# pcb.net
KiCad netlist of a schematic drawn in EasyEDA
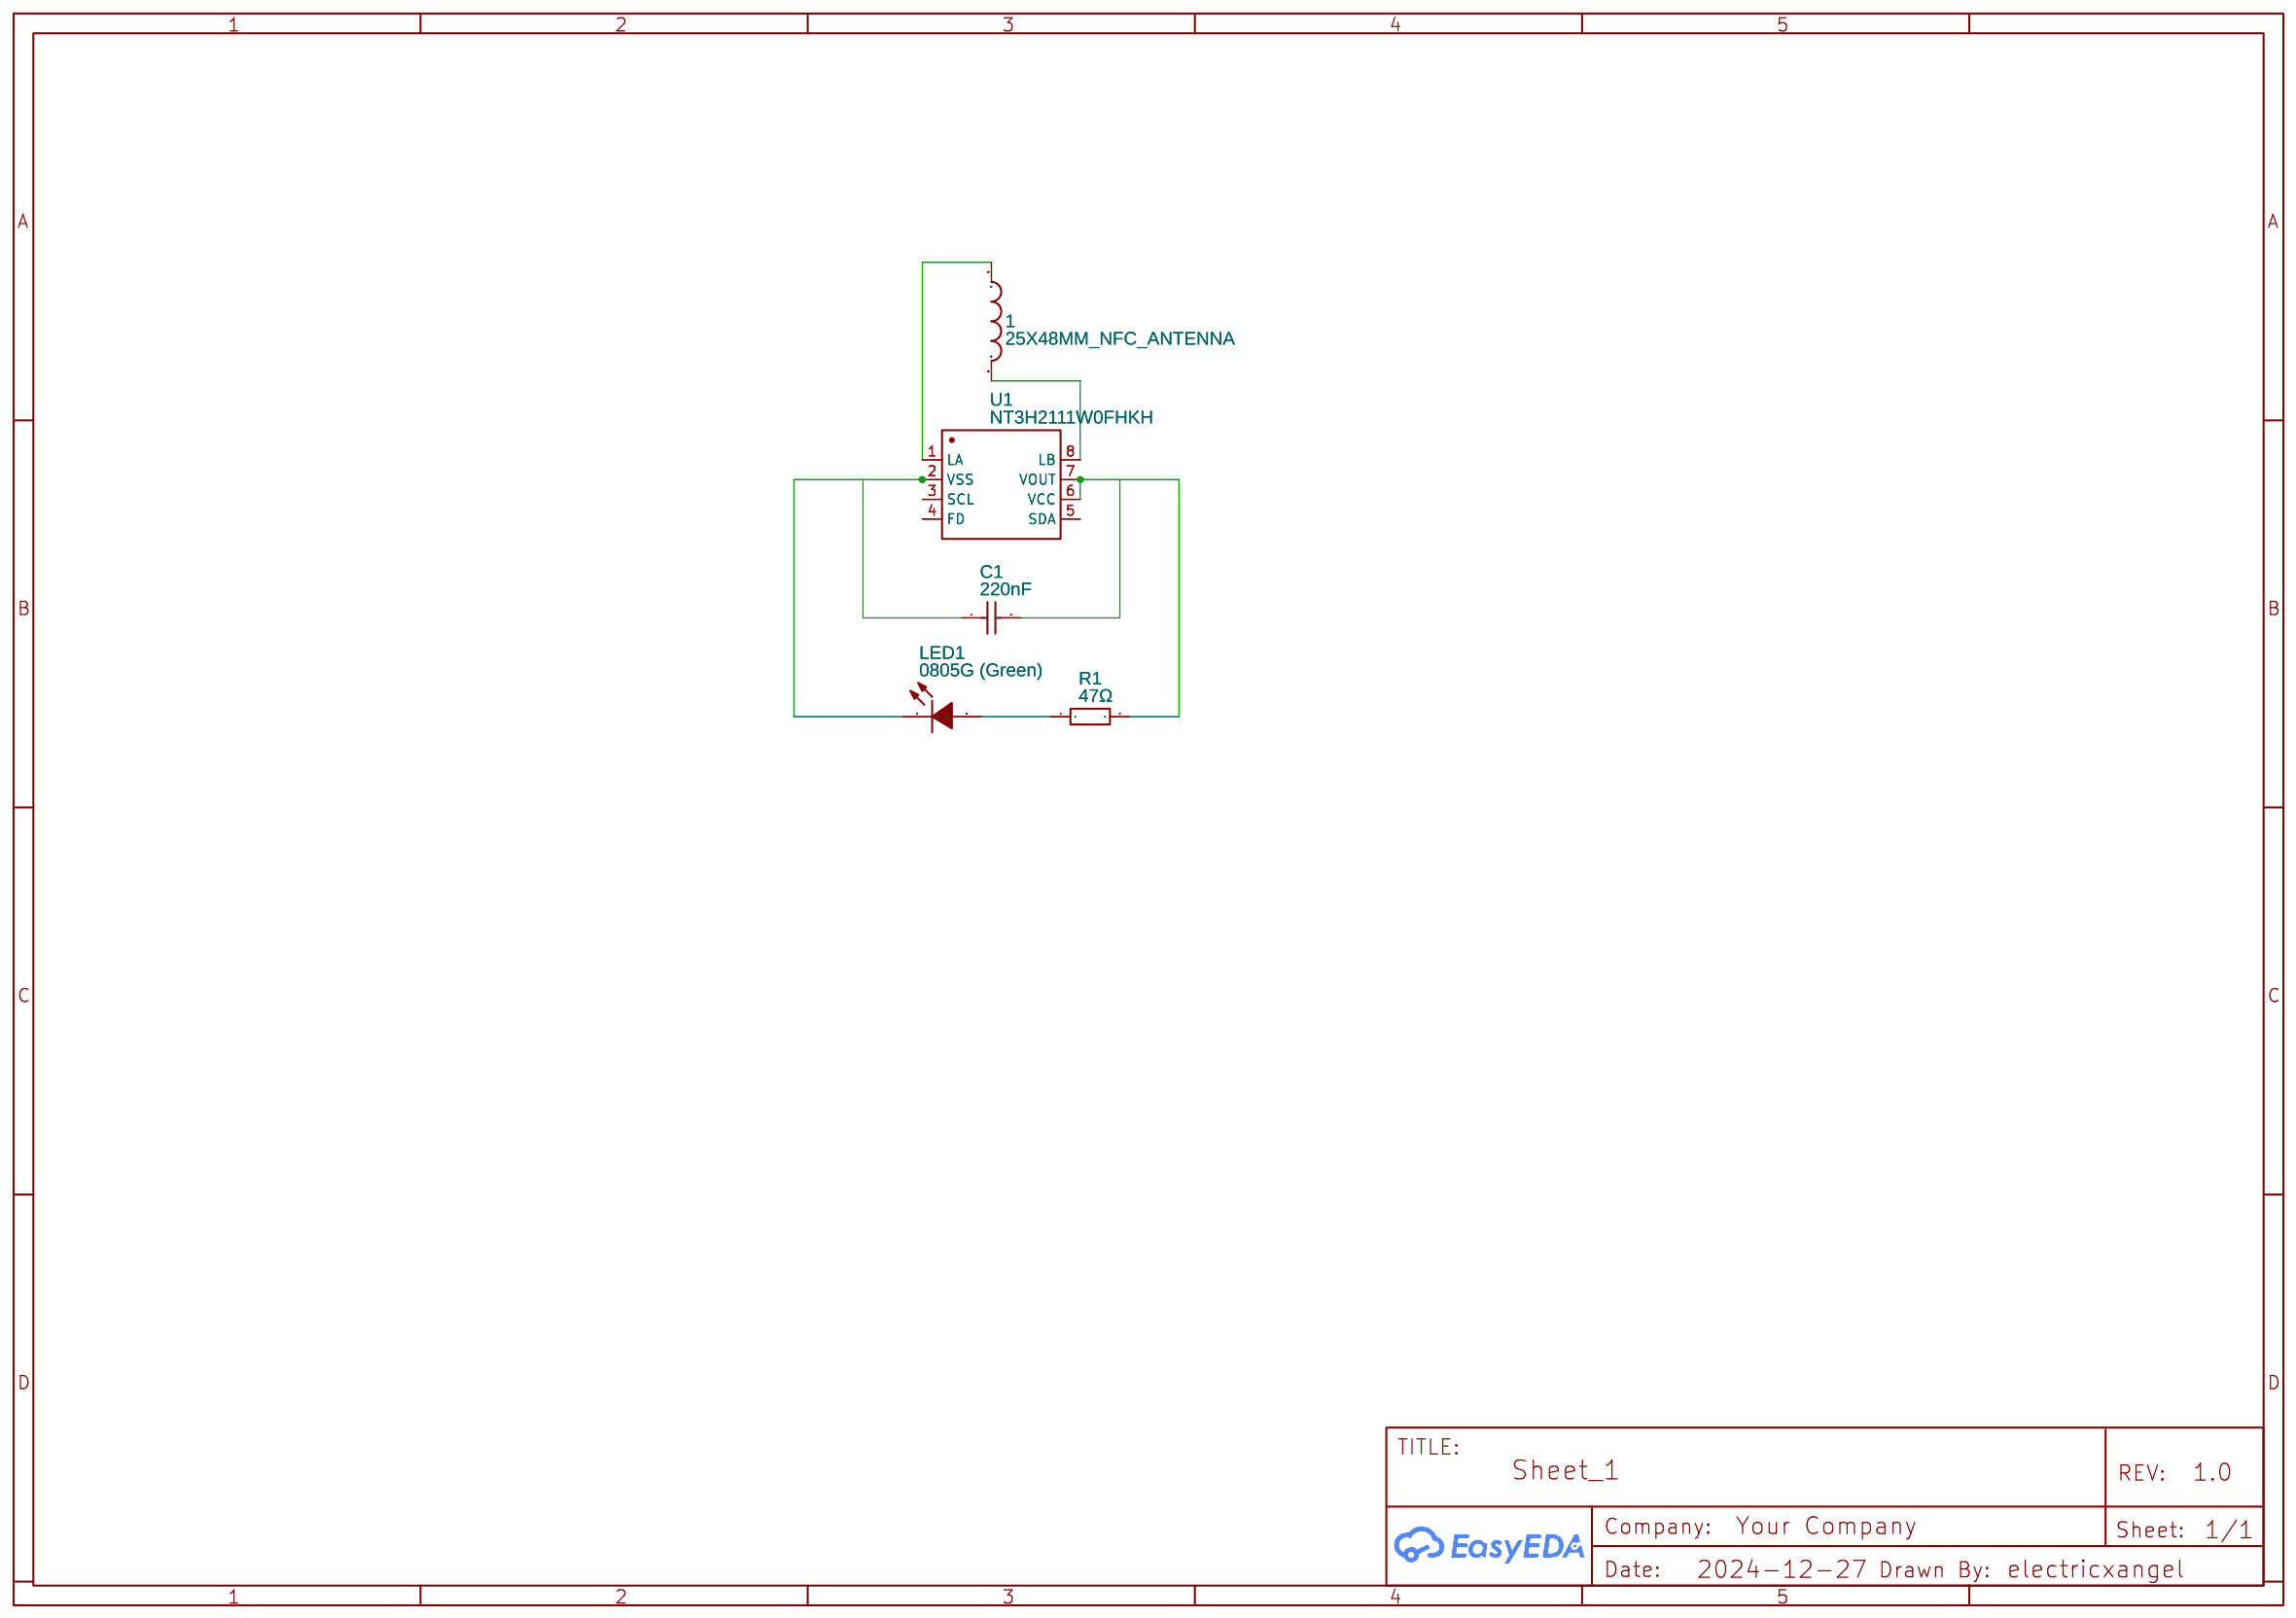
[diagram p0: schematic sheet]

(export (version "E")
  (design (tool "Eeschema 10.0.6"))
  (components
    (comp (ref "1") (value "25X48MM_NFC_ANTENNA") (libsource (lib "") (part "25X48MM_NFC_ANTENNA")))
    (comp (ref "C1")
      (value "220nF")
      (fields
        (field (name "Manufacturer Part") "CL10B224KA8NNNC")
        (field (name "Manufacturer") "SAMSUNG(三星)")
      )
      (libsource (lib "") (part "CL10B224KA8NNNC"))
    )
    (comp (ref "LED1")
      (value "0805G (Green)")
      (fields (field (name "Manufacturer Part") "KT-0805G") (field (name "Manufacturer") "KENTO"))
      (libsource (lib "") (part "0805G (Green)"))
    )
    (comp (ref "R1")
      (value "47Ω")
      (fields
        (field (name "Manufacturer Part") "0603WAF470JT5E")
        (field (name "Manufacturer") "UNI-ROYAL(厚声)")
      )
      (libsource (lib "") (part "0603WAF470JT5E"))
    )
    (comp (ref "U1")
      (value "NT3H2111W0FHKH")
      (fields (field (name "Manufacturer") "NXP(恩智浦)"))
      (libsource (lib "") (part "NT3H2111W0FHKH"))
    )
  )
  (nets
    (net (code "1") (name "Net-(LED1-A)") (class "Default")
      (node (ref "LED1") (pin "1") (pinfunction "A_1") (pintype "unspecified"))
      (node (ref "R1") (pin "1") (pinfunction "1_1") (pintype "input"))
    )
    (net (code "2") (name "Net-(LED1-K)") (class "Default")
      (node (ref "C1") (pin "1") (pinfunction "1_1") (pintype "input"))
      (node (ref "LED1") (pin "2") (pinfunction "K_2") (pintype "unspecified"))
      (node (ref "U1") (pin "2") (pinfunction "VSS_2") (pintype "unspecified"))
    )
    (net (code "3") (name "Net-(U1-LA)") (class "Default")
      (node (ref "1") (pin "P$1") (pinfunction "P$1_P$1") (pintype "bidirectional"))
      (node (ref "U1") (pin "1") (pinfunction "LA_1") (pintype "unspecified"))
    )
    (net (code "4") (name "Net-(U1-LB)") (class "Default")
      (node (ref "1") (pin "P$2") (pinfunction "P$2_P$2") (pintype "bidirectional"))
      (node (ref "U1") (pin "8") (pinfunction "LB_8") (pintype "unspecified"))
    )
    (net (code "5") (name "Net-(U1-VCC)") (class "Default")
      (node (ref "C1") (pin "2") (pinfunction "2_2") (pintype "input"))
      (node (ref "R1") (pin "2") (pinfunction "2_2") (pintype "input"))
      (node (ref "U1") (pin "6") (pinfunction "VCC_6") (pintype "unspecified"))
      (node (ref "U1") (pin "7") (pinfunction "VOUT_7") (pintype "unspecified"))
    )
    (net (code "6") (name "unconnected-(U1-FD-Pad4)") (class "Default")
      (node (ref "U1") (pin "4") (pinfunction "FD_4") (pintype "unspecified"))
    )
    (net (code "7") (name "unconnected-(U1-SCL-Pad3)") (class "Default")
      (node (ref "U1") (pin "3") (pinfunction "SCL_3") (pintype "unspecified"))
    )
    (net (code "8") (name "unconnected-(U1-SDA-Pad5)") (class "Default")
      (node (ref "U1") (pin "5") (pinfunction "SDA_5") (pintype "unspecified"))
    )
  )
)
